# LED0805-2_Sch.net
KiCad netlist of a schematic drawn in Altium Designer
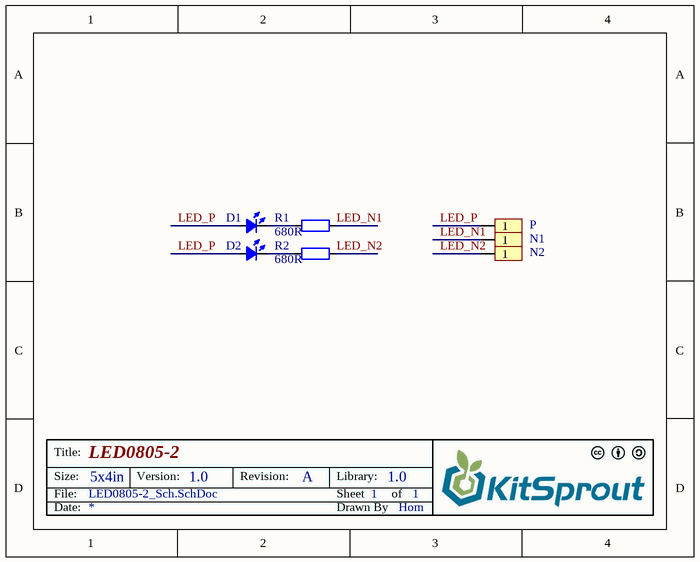
[diagram p0: LED0805-2_Sch.SchDoc]

(export (version "E")
  (design (tool "Eeschema 10.0.6"))
  (components
    (comp (ref "D1")
      (value "LED_0805")
      (footprint "PCB_ActiveLED:LED_0805_BLUE")
      (description "LED")
      (libsource (lib "SCH_Active") (part "LED_0805"))
    )
    (comp (ref "D2")
      (value "LED_0805")
      (footprint "PCB_ActiveLED:LED_0805_BLUE")
      (description "LED")
      (libsource (lib "SCH_Active") (part "LED_0805"))
    )
    (comp (ref "N1")
      (value "HDR-PAD_2.54")
      (footprint "PCB_ConnectorHDR:HDR-PAD_2.54")
      (description "Header")
      (libsource (lib "SCH_ConnectorHDR") (part "HDR-PAD_2.54"))
    )
    (comp (ref "N2")
      (value "HDR-PAD_2.54")
      (footprint "PCB_ConnectorHDR:HDR-PAD_2.54")
      (description "Header")
      (libsource (lib "SCH_ConnectorHDR") (part "HDR-PAD_2.54"))
    )
    (comp (ref "P")
      (value "HDR-PAD_2.54")
      (footprint "PCB_ConnectorHDR:HDR-PAD_2.54")
      (description "Header")
      (libsource (lib "SCH_ConnectorHDR") (part "HDR-PAD_2.54"))
    )
    (comp (ref "R1")
      (value "680R")
      (footprint "PCB_PassiveRes:RES_0805")
      (description "Resistor")
      (fields (field (name "Comment") "Res_0805"))
      (libsource (lib "SCH_Passive") (part "Res_0805"))
    )
    (comp (ref "R2")
      (value "680R")
      (footprint "PCB_PassiveRes:RES_0805")
      (description "Resistor")
      (fields (field (name "Comment") "Res_0805"))
      (libsource (lib "SCH_Passive") (part "Res_0805"))
    )
  )
  (nets
    (net (code "1") (name "/LED_N1") (class "Default")
      (node (ref "N1") (pin "1") (pinfunction "1_1") (pintype "passive"))
      (node (ref "R1") (pin "2") (pinfunction "2_2") (pintype "passive"))
    )
    (net (code "2") (name "/LED_N2") (class "Default")
      (node (ref "N2") (pin "1") (pinfunction "1_1") (pintype "passive"))
      (node (ref "R2") (pin "2") (pinfunction "2_2") (pintype "passive"))
    )
    (net (code "3") (name "/LED_P") (class "Default")
      (node (ref "D1") (pin "1") (pinfunction "A_1") (pintype "passive"))
      (node (ref "D2") (pin "1") (pinfunction "A_1") (pintype "passive"))
      (node (ref "P") (pin "1") (pinfunction "1_1") (pintype "passive"))
    )
    (net (code "4") (name "Net-(D1-K)") (class "Default")
      (node (ref "D1") (pin "2") (pinfunction "K_2") (pintype "passive"))
      (node (ref "R1") (pin "1") (pinfunction "1_1") (pintype "passive"))
    )
    (net (code "5") (name "Net-(D2-K)") (class "Default")
      (node (ref "D2") (pin "2") (pinfunction "K_2") (pintype "passive"))
      (node (ref "R2") (pin "1") (pinfunction "1_1") (pintype "passive"))
    )
  )
)
